# CH32F207VCT6-R1.net
KiCad netlist of a schematic drawn in Altium Designer
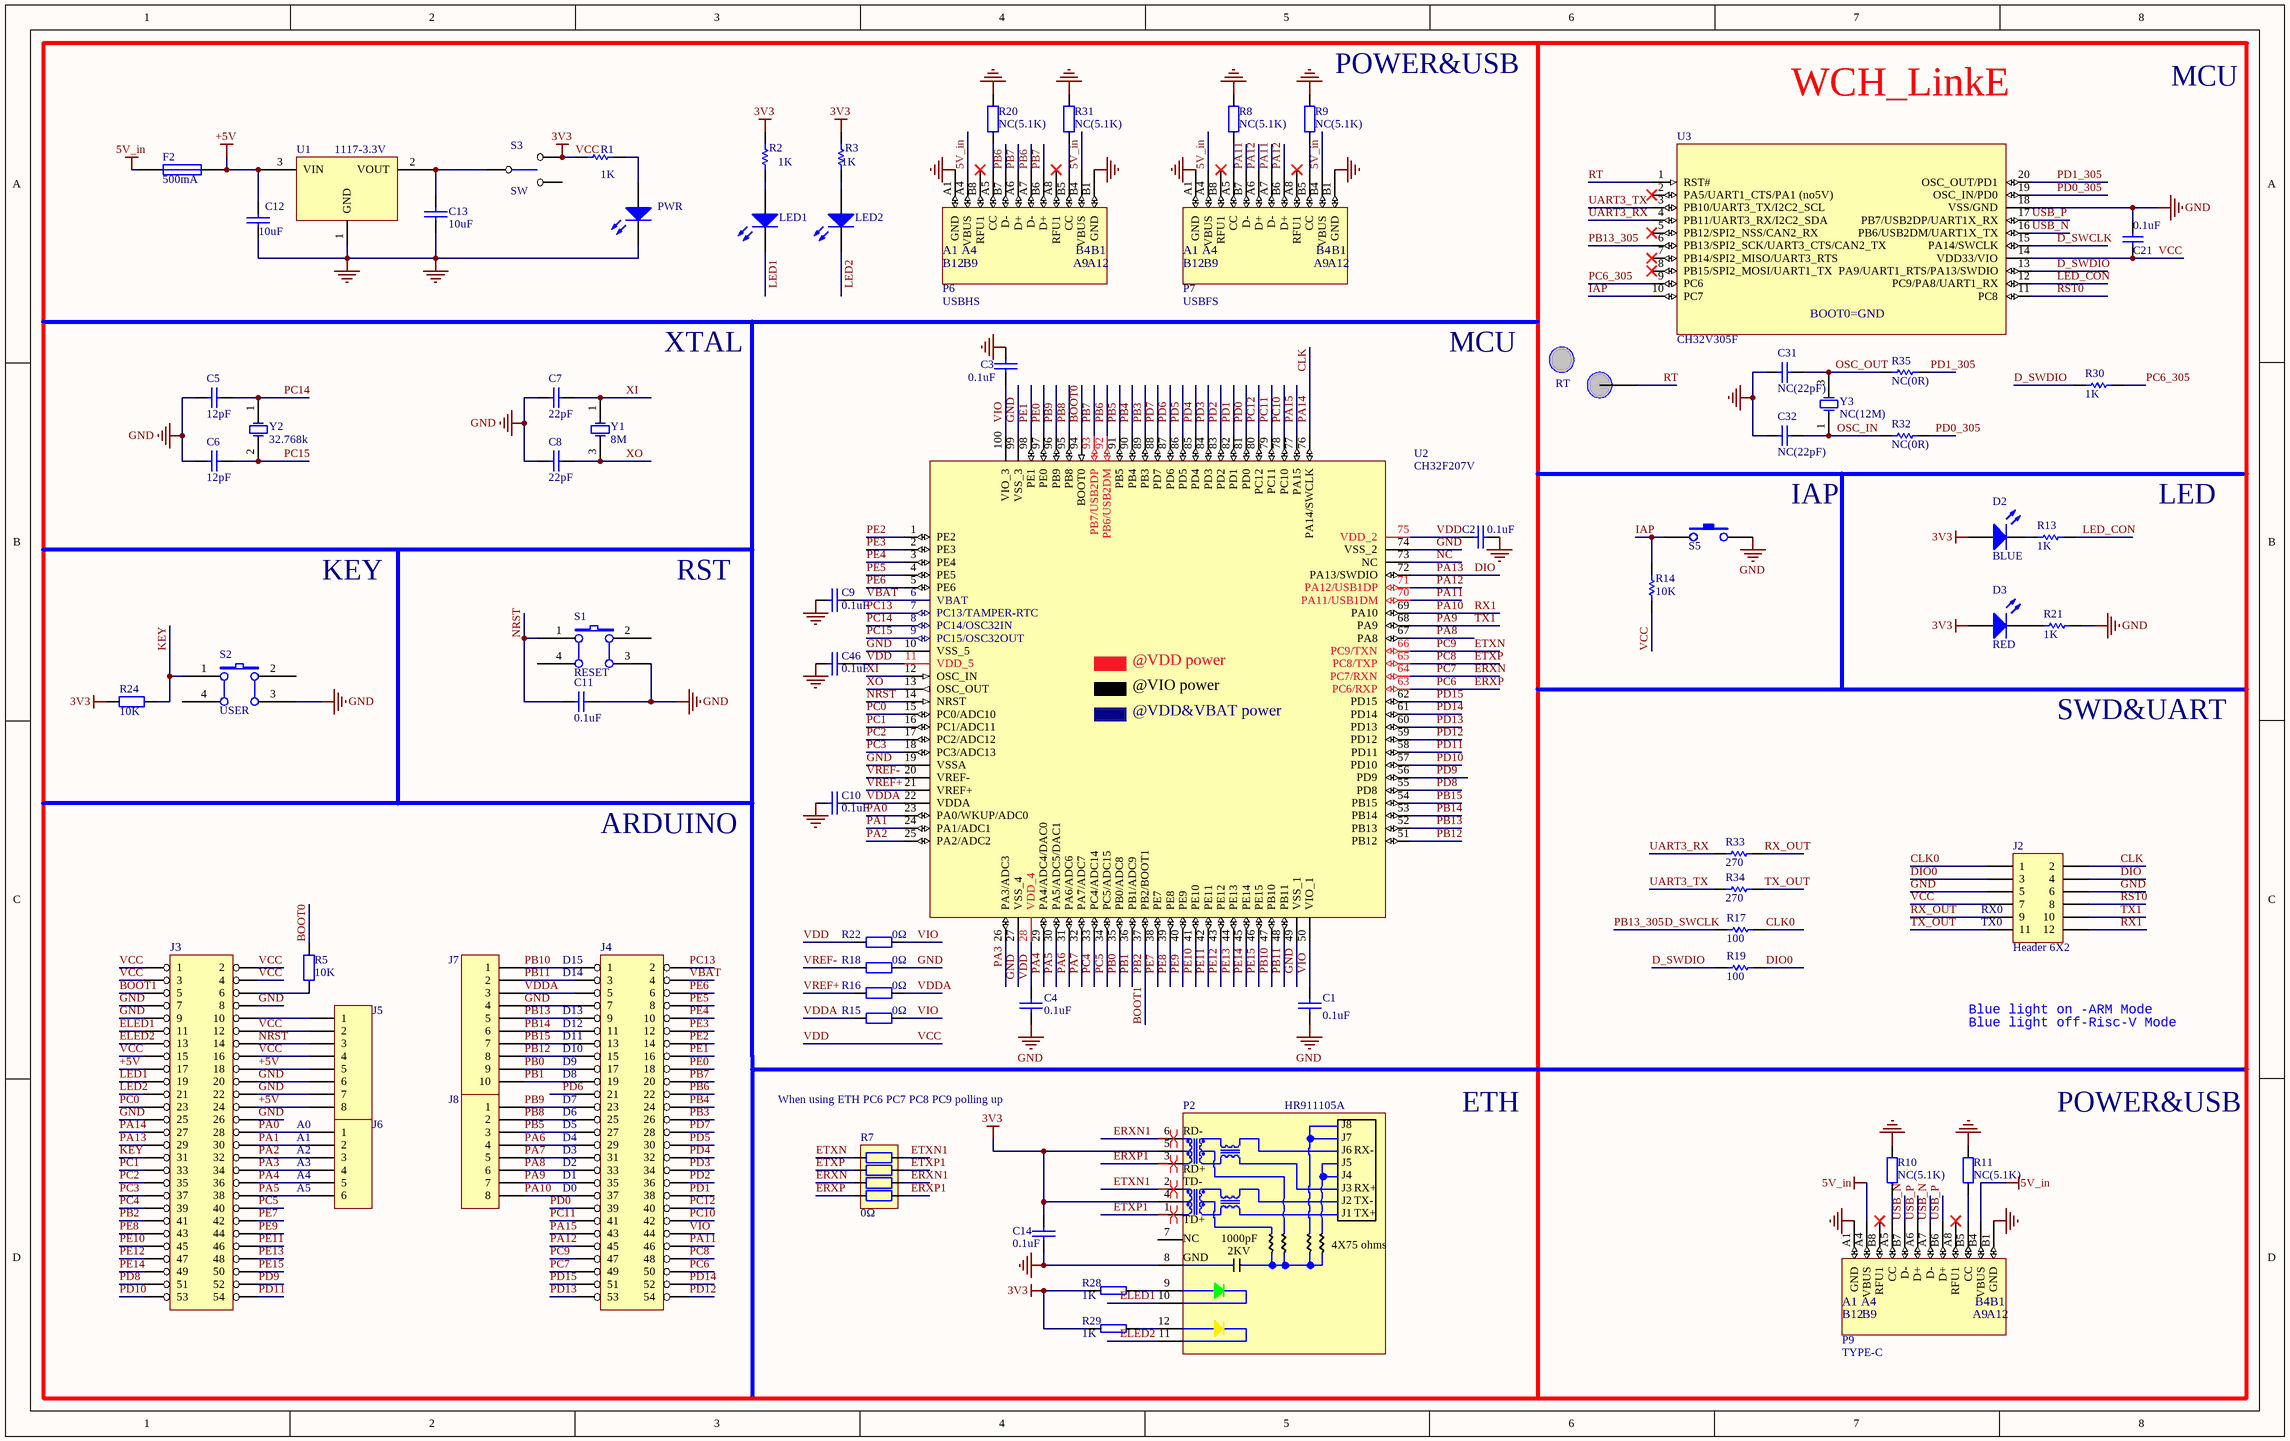
[diagram p0: CH32F207VCT6-R1.SchDoc]

(export (version "E")
  (design (tool "Eeschema 10.0.6"))
  (components
    (comp (ref "C1")
      (value "0.1uF")
      (footprint "0603_C")
      (description "Capacitor")
      (libsource (lib "*") (part "CAP"))
    )
    (comp (ref "C2")
      (value "0.1uF")
      (footprint "0603_C")
      (description "Capacitor")
      (libsource (lib "*") (part "CAP"))
    )
    (comp (ref "C3")
      (value "0.1uF")
      (footprint "0603_C")
      (description "Capacitor")
      (libsource (lib "*") (part "CAP"))
    )
    (comp (ref "C4")
      (value "0.1uF")
      (footprint "0603_C")
      (description "Capacitor")
      (libsource (lib "*") (part "CAP"))
    )
    (comp (ref "C5")
      (value "12pF")
      (footprint "0603_C")
      (description "Capacitor")
      (libsource (lib "Miscellaneous Devices") (part "Cap"))
    )
    (comp (ref "C6")
      (value "12pF")
      (footprint "0603_C")
      (description "Capacitor")
      (libsource (lib "Miscellaneous Devices") (part "Cap"))
    )
    (comp (ref "C7")
      (value "22pF")
      (footprint "0603_C")
      (description "Capacitor")
      (libsource (lib "Miscellaneous Devices") (part "Cap"))
    )
    (comp (ref "C8")
      (value "22pF")
      (footprint "0603_C")
      (description "Capacitor")
      (libsource (lib "Miscellaneous Devices") (part "Cap"))
    )
    (comp (ref "C9")
      (value "0.1uF")
      (footprint "0603_C")
      (description "Capacitor")
      (libsource (lib "*") (part "CAP"))
    )
    (comp (ref "C10")
      (value "0.1uF")
      (footprint "0603_C")
      (description "Capacitor")
      (libsource (lib "*") (part "CAP"))
    )
    (comp (ref "C11")
      (value "0.1uF")
      (footprint "0603_C")
      (description "Capacitor")
      (libsource (lib "Miscellaneous Devices") (part "Cap"))
    )
    (comp (ref "C12")
      (value "10uF")
      (footprint "3216_C")
      (description "Capacitor")
      (libsource (lib "*") (part "CAP"))
    )
    (comp (ref "C13")
      (value "10uF")
      (footprint "3216_C")
      (description "Capacitor")
      (libsource (lib "*") (part "CAP"))
    )
    (comp (ref "C14")
      (value "0.1uF")
      (footprint "0603_C")
      (description "Capacitor")
      (libsource (lib "*") (part "CAP"))
    )
    (comp (ref "C21")
      (value "0.1uF")
      (footprint "0603_C")
      (description "Capacitor")
      (libsource (lib "Miscellaneous Devices") (part "Cap"))
    )
    (comp (ref "C31")
      (value "NC(22pF)")
      (footprint "0603_C")
      (description "Capacitor")
      (libsource (lib "*") (part "Cap"))
    )
    (comp (ref "C32")
      (value "NC(22pF)")
      (footprint "0603_C")
      (description "Capacitor")
      (libsource (lib "*") (part "Cap"))
    )
    (comp (ref "C46")
      (value "0.1uF")
      (footprint "0603_C")
      (description "Capacitor")
      (libsource (lib "*") (part "CAP"))
    )
    (comp (ref "D2")
      (value "BLUE")
      (footprint "0603+")
      (description "Typical RED, GREEN, YELLOW, AMBER GaAs LED")
      (libsource (lib "MYLIB") (part "D0603"))
    )
    (comp (ref "D3")
      (value "RED")
      (footprint "0603+")
      (description "Typical RED, GREEN, YELLOW, AMBER GaAs LED")
      (libsource (lib "MYLIB") (part "D0603"))
    )
    (comp (ref "F2")
      (value "500mA")
      (footprint "0805")
      (description "Fuse")
      (libsource (lib "*") (part "FUSE1"))
    )
    (comp (ref "J2")
      (value "Header 6X2")
      (footprint "IDC12-2.54mm")
      (description "Header, 6-Pin, Dual row")
      (libsource (lib "Miscellaneous Connectors") (part "Header 6X2"))
    )
    (comp (ref "J3")
      (value "HEADER 27x2")
      (footprint "MYPCB:IDC54-2.54MM")
      (description "Header, 27-Pin, Dual row")
      (libsource (lib "wch_sch_others") (part "HEADER 27x2"))
    )
    (comp (ref "J4")
      (value "HEADER 27x2")
      (footprint "MYPCB:IDC54-2.54MM")
      (description "Header, 27-Pin, Dual row")
      (libsource (lib "wch_sch_others") (part "HEADER 27x2"))
    )
    (comp (ref "J5")
      (value "Header 8")
      (footprint "SIP8-2.54mm")
      (description "Header, 8-Pin")
      (libsource (lib "Miscellaneous Connectors") (part "Header 8"))
    )
    (comp (ref "J6")
      (value "Header 6")
      (footprint "SIP6-2.54MM")
      (description "Header, 6-Pin")
      (libsource (lib "Miscellaneous Connectors") (part "Header 6"))
    )
    (comp (ref "J7")
      (value "Header 10")
      (footprint "SIP10-2.54mm")
      (description "Header, 10-Pin")
      (libsource (lib "Miscellaneous Connectors") (part "Header 10"))
    )
    (comp (ref "J8")
      (value "Header 8")
      (footprint "SIP8-2.54mm")
      (description "Header, 8-Pin")
      (libsource (lib "") (part "Header 8_1"))
    )
    (comp (ref "LED1")
      (value "LED1   blue")
      (footprint "0603+")
      (description "Typical INFRARED GaAs LED")
      (libsource (lib "Miscellaneous Devices") (part "LED0"))
    )
    (comp (ref "LED2")
      (value "LED2  blue")
      (footprint "0603+")
      (description "Typical INFRARED GaAs LED")
      (libsource (lib "Miscellaneous Devices") (part "LED0"))
    )
    (comp (ref "P2") (value "HR911105A") (footprint "HR911105A") (libsource (lib "*") (part "HR911105A")))
    (comp (ref "P6")
      (value "USBHS")
      (footprint "TYPE-C-Receptacle-2.0")
      (libsource (lib "*") (part "TYPE-C1"))
    )
    (comp (ref "P7")
      (value "USBFS")
      (footprint "TYPE-C-Receptacle-2.0")
      (libsource (lib "*") (part "TYPE-C1"))
    )
    (comp (ref "P9")
      (value "TYPE-C")
      (footprint "TYPE-C-Receptacle-2.0")
      (libsource (lib "*") (part "TYPE-C1"))
    )
    (comp (ref "PWR")
      (value "POWER  red")
      (footprint "0603+")
      (description "Typical INFRARED GaAs LED")
      (libsource (lib "Miscellaneous Devices") (part "LED0"))
    )
    (comp (ref "R1")
      (value "1K")
      (footprint "0603")
      (description "Semiconductor Resistor")
      (libsource (lib "Miscellaneous Devices") (part "Res Semi"))
    )
    (comp (ref "R2")
      (value "1K")
      (footprint "0603")
      (description "Semiconductor Resistor")
      (libsource (lib "Miscellaneous Devices") (part "Res Semi"))
    )
    (comp (ref "R3")
      (value "1K")
      (footprint "0603")
      (description "Semiconductor Resistor")
      (libsource (lib "Miscellaneous Devices") (part "Res Semi"))
    )
    (comp (ref "R5")
      (value "10K")
      (footprint "0603")
      (description "Resistor")
      (libsource (lib "") (part "Res2_2"))
    )
    (comp (ref "R7")
      (value "0Ω")
      (footprint "RCA-8P4R-0603")
      (description "贴片网络排阻")
      (libsource (lib "wch_sch_others") (part "R-8P4R"))
    )
    (comp (ref "R8")
      (value "NC(5.1K)")
      (footprint "0603")
      (description "Resistor")
      (libsource (lib "Miscellaneous Devices") (part "Res2"))
    )
    (comp (ref "R9")
      (value "NC(5.1K)")
      (footprint "0603")
      (description "Resistor")
      (libsource (lib "Miscellaneous Devices") (part "Res2"))
    )
    (comp (ref "R10")
      (value "NC(5.1K)")
      (footprint "0603")
      (description "Resistor")
      (libsource (lib "") (part "Res2_2"))
    )
    (comp (ref "R11")
      (value "NC(5.1K)")
      (footprint "0603")
      (description "Resistor")
      (libsource (lib "") (part "Res2_2"))
    )
    (comp (ref "R13")
      (value "1K")
      (footprint "0603")
      (description "Resistor")
      (libsource (lib "MYLIB") (part "0603-1"))
    )
    (comp (ref "R14")
      (value "10K")
      (footprint "0603")
      (description "Resistor")
      (libsource (lib "MYLIB") (part "0603-1"))
    )
    (comp (ref "R15")
      (value "0Ω")
      (footprint "0603")
      (description "Resistor")
      (libsource (lib "") (part "Res2_1"))
    )
    (comp (ref "R16")
      (value "0Ω")
      (footprint "0603")
      (description "Resistor")
      (libsource (lib "") (part "Res2_1"))
    )
    (comp (ref "R17")
      (value "100")
      (footprint "0603")
      (description "Resistor")
      (libsource (lib "MYLIB") (part "0603-1"))
    )
    (comp (ref "R18")
      (value "0Ω")
      (footprint "0603")
      (description "Resistor")
      (libsource (lib "") (part "Res2_1"))
    )
    (comp (ref "R19")
      (value "100")
      (footprint "0603")
      (description "Resistor")
      (libsource (lib "MYLIB") (part "0603-1"))
    )
    (comp (ref "R20")
      (value "NC(5.1K)")
      (footprint "0603")
      (description "Resistor")
      (libsource (lib "Miscellaneous Devices") (part "Res2"))
    )
    (comp (ref "R21")
      (value "1K")
      (footprint "0603")
      (description "Resistor")
      (libsource (lib "MYLIB") (part "0603-1"))
    )
    (comp (ref "R22")
      (value "0Ω")
      (footprint "0603")
      (description "Resistor")
      (libsource (lib "") (part "Res2_1"))
    )
    (comp (ref "R24")
      (value "10K")
      (footprint "0603")
      (description "Resistor")
      (libsource (lib "") (part "Res2_1"))
    )
    (comp (ref "R28") (value "1K") (footprint "0603") (libsource (lib "wch_sch_others") (part "RES")))
    (comp (ref "R29") (value "1K") (footprint "0603") (libsource (lib "wch_sch_others") (part "RES")))
    (comp (ref "R30")
      (value "1K")
      (footprint "0603")
      (description "Resistor")
      (libsource (lib "MYLIB") (part "0603-1"))
    )
    (comp (ref "R31")
      (value "NC(5.1K)")
      (footprint "0603")
      (description "Resistor")
      (libsource (lib "Miscellaneous Devices") (part "Res2"))
    )
    (comp (ref "R32")
      (value "NC(0R)")
      (footprint "0603")
      (description "Resistor")
      (libsource (lib "MYLIB") (part "0603-1"))
    )
    (comp (ref "R33")
      (value "270")
      (footprint "0603")
      (description "Resistor")
      (libsource (lib "MYLIB") (part "0603-1"))
    )
    (comp (ref "R34")
      (value "270")
      (footprint "0603")
      (description "Resistor")
      (libsource (lib "MYLIB") (part "0603-1"))
    )
    (comp (ref "R35")
      (value "NC(0R)")
      (footprint "0603")
      (description "Resistor")
      (libsource (lib "MYLIB") (part "0603-1"))
    )
    (comp (ref "RT")
      (value "Testpoint")
      (footprint "TESTPOINT1")
      (description "测试点")
      (libsource (lib "wch_sch_others") (part "Testpoint"))
    )
    (comp (ref "S1")
      (value "RESET")
      (footprint "KEYX")
      (description "SE PUSHBUTTON")
      (libsource (lib "Documents") (part "SW PUSHBUTTON"))
    )
    (comp (ref "S2")
      (value "USER")
      (footprint "KEYX")
      (description "SE PUSHBUTTON")
      (libsource (lib "Documents") (part "SW PUSHBUTTON"))
    )
    (comp (ref "S3") (value "SW") (footprint "SW1") (libsource (lib "MYSCH") (part "SW")))
    (comp (ref "S5") (value "KEY") (footprint "贴片按键") (libsource (lib "*") (part "KEY")))
    (comp (ref "U1")
      (value "1117-3.3V")
      (footprint "SOT-223")
      (libsource (lib "wch_sch_others") (part "1117-3.3V"))
    )
    (comp (ref "U2")
      (value "CH32F207V")
      (footprint "LQFP100")
      (description "ARM M3 HD-MCU, 144MHz, USB_480M, USB OTG, 1000M Ethernet MAC, 2*CAN")
      (libsource (lib "CHXXX") (part "CH32F207V"))
    )
    (comp (ref "U3")
      (value "CH32V305F")
      (footprint "TSSOP20")
      (description "RISC-V FPU HD-MCU, 144MHz, USB_480M, CAN, UART*2, SPI")
      (libsource (lib "CHXXX") (part "CH32V305F"))
    )
    (comp (ref "Y1")
      (value "8M")
      (footprint "XT3225")
      (description "Crystal Oscillator")
      (libsource (lib "Miscellaneous Devices") (part "XTAL"))
    )
    (comp (ref "Y2")
      (value "32.768k")
      (footprint "FC-135")
      (description "Crystal Oscillator")
      (libsource (lib "") (part "XTAL_1"))
    )
    (comp (ref "Y3")
      (value "NC(12M)")
      (footprint "XT3225")
      (description "Crystal Oscillator")
      (libsource (lib "*") (part "XTAL"))
    )
  )
  (nets
    (net (code "1") (name "+5V") (class "Default")
      (node (ref "C12") (pin "1") (pinfunction "1_1") (pintype "passive"))
      (node (ref "F2") (pin "2") (pinfunction "2_2") (pintype "passive"))
      (node (ref "J3") (pin "17") (pinfunction "17_17") (pintype "passive"))
      (node (ref "J3") (pin "18") (pinfunction "18_18") (pintype "passive"))
      (node (ref "J3") (pin "24") (pinfunction "24_24") (pintype "passive"))
      (node (ref "J5") (pin "5") (pinfunction "5_5") (pintype "passive"))
      (node (ref "J5") (pin "8") (pinfunction "8_8") (pintype "passive"))
      (node (ref "U1") (pin "3") (pinfunction "VIN_3") (pintype "passive"))
    )
    (net (code "2") (name "/BOOT0") (class "Default")
      (node (ref "R5") (pin "2") (pinfunction "2_2") (pintype "passive"))
      (node (ref "U2") (pin "94") (pinfunction "BOOT0_94") (pintype "input"))
    )
    (net (code "3") (name "/BOOT1") (class "Default")
      (node (ref "J3") (pin "41") (pinfunction "41_41") (pintype "passive"))
      (node (ref "J3") (pin "5") (pinfunction "5_5") (pintype "passive"))
      (node (ref "U2") (pin "37") (pinfunction "PB2/BOOT1_37") (pintype "bidirectional"))
    )
    (net (code "4") (name "/CLK") (class "Default")
      (node (ref "J2") (pin "2") (pinfunction "2_2") (pintype "passive"))
      (node (ref "J3") (pin "27") (pinfunction "27_27") (pintype "passive"))
      (node (ref "U2") (pin "76") (pinfunction "PA14/SWCLK_76") (pintype "bidirectional"))
    )
    (net (code "5") (name "/CLK0") (class "Default")
      (node (ref "J2") (pin "1") (pinfunction "1_1") (pintype "passive"))
      (node (ref "R17") (pin "1") (pinfunction "1_1") (pintype "passive"))
    )
    (net (code "6") (name "/DIO") (class "Default")
      (node (ref "J2") (pin "4") (pinfunction "4_4") (pintype "passive"))
      (node (ref "J3") (pin "29") (pinfunction "29_29") (pintype "passive"))
      (node (ref "U2") (pin "72") (pinfunction "PA13/SWDIO_72") (pintype "bidirectional"))
    )
    (net (code "7") (name "/DIO0") (class "Default")
      (node (ref "J2") (pin "3") (pinfunction "3_3") (pintype "passive"))
      (node (ref "R19") (pin "1") (pinfunction "1_1") (pintype "passive"))
    )
    (net (code "8") (name "/D_SWCLK") (class "Default")
      (node (ref "R17") (pin "2") (pinfunction "2_2") (pintype "passive"))
      (node (ref "U3") (pin "15") (pinfunction "PA14/SWCLK_15") (pintype "bidirectional"))
      (node (ref "U3") (pin "6") (pinfunction "PB13/SPI2_SCK/UART3_CTS/CAN2_TX_6") (pintype "bidirectional"))
    )
    (net (code "9") (name "/D_SWDIO") (class "Default")
      (node (ref "R19") (pin "2") (pinfunction "2_2") (pintype "passive"))
      (node (ref "R30") (pin "1") (pinfunction "1_1") (pintype "passive"))
      (node (ref "U3") (pin "13") (pinfunction "PA9/UART1_RTS/PA13/SWDIO_13") (pintype "bidirectional"))
    )
    (net (code "10") (name "/ELED1") (class "Default")
      (node (ref "J3") (pin "11") (pinfunction "11_11") (pintype "passive"))
      (node (ref "P2") (pin "10") (pintype "passive"))
    )
    (net (code "11") (name "/ELED2") (class "Default")
      (node (ref "J3") (pin "13") (pinfunction "13_13") (pintype "passive"))
      (node (ref "P2") (pin "11") (pintype "passive"))
    )
    (net (code "12") (name "/ERXN") (class "Default")
      (node (ref "J4") (pin "49") (pinfunction "49_49") (pintype "passive"))
      (node (ref "R7") (pin "3") (pinfunction "3_3") (pintype "passive"))
      (node (ref "U2") (pin "64") (pinfunction "PC7/RXN_64") (pintype "bidirectional"))
    )
    (net (code "13") (name "/ERXN1") (class "Default")
      (node (ref "P2") (pin "6") (pintype "passive"))
      (node (ref "R7") (pin "6") (pinfunction "6_6") (pintype "passive"))
    )
    (net (code "14") (name "/ERXP") (class "Default")
      (node (ref "J4") (pin "50") (pinfunction "50_50") (pintype "passive"))
      (node (ref "R7") (pin "4") (pinfunction "4_4") (pintype "passive"))
      (node (ref "U2") (pin "63") (pinfunction "PC6/RXP_63") (pintype "bidirectional"))
    )
    (net (code "15") (name "/ERXP1") (class "Default")
      (node (ref "P2") (pin "3") (pintype "passive"))
      (node (ref "R7") (pin "5") (pinfunction "5_5") (pintype "passive"))
    )
    (net (code "16") (name "/ETXN") (class "Default")
      (node (ref "J4") (pin "47") (pinfunction "47_47") (pintype "passive"))
      (node (ref "R7") (pin "1") (pinfunction "1_1") (pintype "passive"))
      (node (ref "U2") (pin "66") (pinfunction "PC9/TXN_66") (pintype "bidirectional"))
    )
    (net (code "17") (name "/ETXN1") (class "Default")
      (node (ref "P2") (pin "2") (pintype "passive"))
      (node (ref "R7") (pin "8") (pinfunction "8_8") (pintype "passive"))
    )
    (net (code "18") (name "/ETXP") (class "Default")
      (node (ref "J4") (pin "48") (pinfunction "48_48") (pintype "passive"))
      (node (ref "R7") (pin "2") (pinfunction "2_2") (pintype "passive"))
      (node (ref "U2") (pin "65") (pinfunction "PC8/TXP_65") (pintype "bidirectional"))
    )
    (net (code "19") (name "/ETXP1") (class "Default")
      (node (ref "P2") (pin "1") (pintype "passive"))
      (node (ref "R7") (pin "7") (pinfunction "7_7") (pintype "passive"))
    )
    (net (code "20") (name "/IAP") (class "Default")
      (node (ref "R14") (pin "1") (pinfunction "1_1") (pintype "passive"))
      (node (ref "S5") (pin "1") (pinfunction "1_1") (pintype "passive"))
      (node (ref "U3") (pin "10") (pinfunction "PC7_10") (pintype "bidirectional"))
    )
    (net (code "21") (name "/KEY") (class "Default")
      (node (ref "J3") (pin "31") (pinfunction "31_31") (pintype "passive"))
      (node (ref "R24") (pin "1") (pinfunction "1_1") (pintype "passive"))
      (node (ref "S2") (pin "1") (pinfunction "A0_1") (pintype "passive"))
    )
    (net (code "22") (name "/LED1") (class "Default")
      (node (ref "J3") (pin "19") (pinfunction "19_19") (pintype "passive"))
      (node (ref "LED1") (pin "2") (pinfunction "K_2") (pintype "passive"))
    )
    (net (code "23") (name "/LED2") (class "Default")
      (node (ref "J3") (pin "21") (pinfunction "21_21") (pintype "passive"))
      (node (ref "LED2") (pin "2") (pinfunction "K_2") (pintype "passive"))
    )
    (net (code "24") (name "/LED_CON") (class "Default")
      (node (ref "R13") (pin "1") (pinfunction "1_1") (pintype "passive"))
      (node (ref "U3") (pin "12") (pinfunction "PC9/PA8/UART1_RX_12") (pintype "bidirectional"))
    )
    (net (code "25") (name "/NC") (class "Default")
      (node (ref "U2") (pin "73") (pinfunction "NC_73") (pintype "tri_state"))
    )
    (net (code "26") (name "/NRST") (class "Default")
      (node (ref "C11") (pin "2") (pinfunction "2_2") (pintype "passive"))
      (node (ref "J3") (pin "14") (pinfunction "14_14") (pintype "passive"))
      (node (ref "J5") (pin "3") (pinfunction "3_3") (pintype "passive"))
      (node (ref "S1") (pin "1") (pinfunction "A0_1") (pintype "passive"))
      (node (ref "U2") (pin "14") (pinfunction "NRST_14") (pintype "input"))
    )
    (net (code "27") (name "/OSC_IN") (class "Default")
      (node (ref "C32") (pin "2") (pinfunction "2_2") (pintype "passive"))
      (node (ref "R32") (pin "2") (pinfunction "2_2") (pintype "passive"))
      (node (ref "Y3") (pin "1") (pinfunction "OSC1_1") (pintype "passive"))
    )
    (net (code "28") (name "/OSC_OUT") (class "Default")
      (node (ref "C31") (pin "2") (pinfunction "2_2") (pintype "passive"))
      (node (ref "R35") (pin "2") (pinfunction "2_2") (pintype "passive"))
      (node (ref "Y3") (pin "3") (pinfunction "OSC2_3") (pintype "passive"))
    )
    (net (code "29") (name "/PA0") (class "Default")
      (node (ref "J3") (pin "28") (pinfunction "28_28") (pintype "passive"))
      (node (ref "J6") (pin "1") (pinfunction "1_1") (pintype "passive"))
      (node (ref "U2") (pin "23") (pinfunction "PA0/WKUP/ADC0_23") (pintype "bidirectional"))
    )
    (net (code "30") (name "/PA1") (class "Default")
      (node (ref "J3") (pin "30") (pinfunction "30_30") (pintype "passive"))
      (node (ref "J6") (pin "2") (pinfunction "2_2") (pintype "passive"))
      (node (ref "U2") (pin "24") (pinfunction "PA1/ADC1_24") (pintype "bidirectional"))
    )
    (net (code "31") (name "/PA2") (class "Default")
      (node (ref "J3") (pin "32") (pinfunction "32_32") (pintype "passive"))
      (node (ref "J6") (pin "3") (pinfunction "3_3") (pintype "passive"))
      (node (ref "U2") (pin "25") (pinfunction "PA2/ADC2_25") (pintype "bidirectional"))
    )
    (net (code "32") (name "/PA3") (class "Default")
      (node (ref "J3") (pin "34") (pinfunction "34_34") (pintype "passive"))
      (node (ref "J6") (pin "4") (pinfunction "4_4") (pintype "passive"))
      (node (ref "U2") (pin "26") (pinfunction "PA3/ADC3_26") (pintype "bidirectional"))
    )
    (net (code "33") (name "/PA4") (class "Default")
      (node (ref "J3") (pin "36") (pinfunction "36_36") (pintype "passive"))
      (node (ref "J6") (pin "5") (pinfunction "5_5") (pintype "passive"))
      (node (ref "U2") (pin "29") (pinfunction "PA4/ADC4/DAC0_29") (pintype "bidirectional"))
    )
    (net (code "34") (name "/PA5") (class "Default")
      (node (ref "J3") (pin "38") (pinfunction "38_38") (pintype "passive"))
      (node (ref "J6") (pin "6") (pinfunction "6_6") (pintype "passive"))
      (node (ref "U2") (pin "30") (pinfunction "PA5/ADC5/DAC1_30") (pintype "bidirectional"))
    )
    (net (code "35") (name "/PA6") (class "Default")
      (node (ref "J4") (pin "29") (pinfunction "29_29") (pintype "passive"))
      (node (ref "J8") (pin "4") (pinfunction "4_4") (pintype "passive"))
      (node (ref "U2") (pin "31") (pinfunction "PA6/ADC6_31") (pintype "bidirectional"))
    )
    (net (code "36") (name "/PA7") (class "Default")
      (node (ref "J4") (pin "31") (pinfunction "31_31") (pintype "passive"))
      (node (ref "J8") (pin "5") (pinfunction "5_5") (pintype "passive"))
      (node (ref "U2") (pin "32") (pinfunction "PA7/ADC7_32") (pintype "bidirectional"))
    )
    (net (code "37") (name "/PA8") (class "Default")
      (node (ref "J4") (pin "33") (pinfunction "33_33") (pintype "passive"))
      (node (ref "J8") (pin "6") (pinfunction "6_6") (pintype "passive"))
      (node (ref "U2") (pin "67") (pinfunction "PA8_67") (pintype "bidirectional"))
    )
    (net (code "38") (name "/PA9") (class "Default")
      (node (ref "J2") (pin "10") (pinfunction "10_10") (pintype "passive"))
      (node (ref "J4") (pin "35") (pinfunction "35_35") (pintype "passive"))
      (node (ref "J8") (pin "7") (pinfunction "7_7") (pintype "passive"))
      (node (ref "U2") (pin "68") (pinfunction "PA9_68") (pintype "bidirectional"))
    )
    (net (code "39") (name "/PA10") (class "Default")
      (node (ref "J2") (pin "12") (pinfunction "12_12") (pintype "passive"))
      (node (ref "J4") (pin "37") (pinfunction "37_37") (pintype "passive"))
      (node (ref "J8") (pin "8") (pinfunction "8_8") (pintype "passive"))
      (node (ref "U2") (pin "69") (pinfunction "PA10_69") (pintype "bidirectional"))
    )
    (net (code "40") (name "/PA11") (class "Default")
      (node (ref "J4") (pin "46") (pinfunction "46_46") (pintype "passive"))
      (node (ref "P7") (pin "A7") (pinfunction "D-_A7") (pintype "bidirectional"))
      (node (ref "P7") (pin "B7") (pinfunction "D-_B7") (pintype "bidirectional"))
      (node (ref "U2") (pin "70") (pinfunction "PA11/USB1DM_70") (pintype "bidirectional"))
    )
    (net (code "41") (name "/PA12") (class "Default")
      (node (ref "J4") (pin "45") (pinfunction "45_45") (pintype "passive"))
      (node (ref "P7") (pin "A6") (pinfunction "D+_A6") (pintype "bidirectional"))
      (node (ref "P7") (pin "B6") (pinfunction "D+_B6") (pintype "bidirectional"))
      (node (ref "U2") (pin "71") (pinfunction "PA12/USB1DP_71") (pintype "bidirectional"))
    )
    (net (code "42") (name "/PA15") (class "Default")
      (node (ref "J4") (pin "43") (pinfunction "43_43") (pintype "passive"))
      (node (ref "U2") (pin "77") (pinfunction "PA15_77") (pintype "bidirectional"))
    )
    (net (code "43") (name "/PB0") (class "Default")
      (node (ref "J4") (pin "17") (pinfunction "17_17") (pintype "passive"))
      (node (ref "J7") (pin "9") (pinfunction "9_9") (pintype "passive"))
      (node (ref "U2") (pin "35") (pinfunction "PB0/ADC8_35") (pintype "bidirectional"))
    )
    (net (code "44") (name "/PB1") (class "Default")
      (node (ref "J4") (pin "19") (pinfunction "19_19") (pintype "passive"))
      (node (ref "J7") (pin "10") (pinfunction "10_10") (pintype "passive"))
      (node (ref "U2") (pin "36") (pinfunction "PB1/ADC9_36") (pintype "bidirectional"))
    )
    (net (code "45") (name "/PB3") (class "Default")
      (node (ref "J4") (pin "26") (pinfunction "26_26") (pintype "passive"))
      (node (ref "U2") (pin "89") (pinfunction "PB3_89") (pintype "bidirectional"))
    )
    (net (code "46") (name "/PB4") (class "Default")
      (node (ref "J4") (pin "24") (pinfunction "24_24") (pintype "passive"))
      (node (ref "U2") (pin "90") (pinfunction "PB4_90") (pintype "bidirectional"))
    )
    (net (code "47") (name "/PB5") (class "Default")
      (node (ref "J4") (pin "27") (pinfunction "27_27") (pintype "passive"))
      (node (ref "J8") (pin "3") (pinfunction "3_3") (pintype "passive"))
      (node (ref "U2") (pin "91") (pinfunction "PB5_91") (pintype "bidirectional"))
    )
    (net (code "48") (name "/PB6") (class "Default")
      (node (ref "J4") (pin "22") (pinfunction "22_22") (pintype "passive"))
      (node (ref "P6") (pin "A7") (pinfunction "D-_A7") (pintype "bidirectional"))
      (node (ref "P6") (pin "B7") (pinfunction "D-_B7") (pintype "bidirectional"))
      (node (ref "U2") (pin "92") (pinfunction "PB6/USB2DM_92") (pintype "bidirectional"))
    )
    (net (code "49") (name "/PB7") (class "Default")
      (node (ref "J4") (pin "20") (pinfunction "20_20") (pintype "passive"))
      (node (ref "P6") (pin "A6") (pinfunction "D+_A6") (pintype "bidirectional"))
      (node (ref "P6") (pin "B6") (pinfunction "D+_B6") (pintype "bidirectional"))
      (node (ref "U2") (pin "93") (pinfunction "PB7/USB2DP_93") (pintype "bidirectional"))
    )
    (net (code "50") (name "/PB8") (class "Default")
      (node (ref "J4") (pin "25") (pinfunction "25_25") (pintype "passive"))
      (node (ref "J8") (pin "2") (pinfunction "2_2") (pintype "passive"))
      (node (ref "U2") (pin "95") (pinfunction "PB8_95") (pintype "bidirectional"))
    )
    (net (code "51") (name "/PB9") (class "Default")
      (node (ref "J4") (pin "23") (pinfunction "23_23") (pintype "passive"))
      (node (ref "J8") (pin "1") (pinfunction "1_1") (pintype "passive"))
      (node (ref "U2") (pin "96") (pinfunction "PB9_96") (pintype "bidirectional"))
    )
    (net (code "52") (name "/PB10") (class "Default")
      (node (ref "J4") (pin "1") (pinfunction "1_1") (pintype "passive"))
      (node (ref "J7") (pin "1") (pinfunction "1_1") (pintype "passive"))
      (node (ref "U2") (pin "47") (pinfunction "PB10_47") (pintype "bidirectional"))
    )
    (net (code "53") (name "/PB11") (class "Default")
      (node (ref "J4") (pin "3") (pinfunction "3_3") (pintype "passive"))
      (node (ref "J7") (pin "2") (pinfunction "2_2") (pintype "passive"))
      (node (ref "U2") (pin "48") (pinfunction "PB11_48") (pintype "bidirectional"))
    )
    (net (code "54") (name "/PB12") (class "Default")
      (node (ref "J4") (pin "15") (pinfunction "15_15") (pintype "passive"))
      (node (ref "J7") (pin "8") (pinfunction "8_8") (pintype "passive"))
      (node (ref "U2") (pin "51") (pinfunction "PB12_51") (pintype "bidirectional"))
    )
    (net (code "55") (name "/PB13") (class "Default")
      (node (ref "J4") (pin "9") (pinfunction "9_9") (pintype "passive"))
      (node (ref "J7") (pin "5") (pinfunction "5_5") (pintype "passive"))
      (node (ref "U2") (pin "52") (pinfunction "PB13_52") (pintype "bidirectional"))
    )
    (net (code "56") (name "/PB14") (class "Default")
      (node (ref "J4") (pin "11") (pinfunction "11_11") (pintype "passive"))
      (node (ref "J7") (pin "6") (pinfunction "6_6") (pintype "passive"))
      (node (ref "U2") (pin "53") (pinfunction "PB14_53") (pintype "bidirectional"))
    )
    (net (code "57") (name "/PB15") (class "Default")
      (node (ref "J4") (pin "13") (pinfunction "13_13") (pintype "passive"))
      (node (ref "J7") (pin "7") (pinfunction "7_7") (pintype "passive"))
      (node (ref "U2") (pin "54") (pinfunction "PB15_54") (pintype "bidirectional"))
    )
    (net (code "58") (name "/PC0") (class "Default")
      (node (ref "J3") (pin "23") (pinfunction "23_23") (pintype "passive"))
      (node (ref "U2") (pin "15") (pinfunction "PC0/ADC10_15") (pintype "bidirectional"))
    )
    (net (code "59") (name "/PC1") (class "Default")
      (node (ref "J3") (pin "33") (pinfunction "33_33") (pintype "passive"))
      (node (ref "U2") (pin "16") (pinfunction "PC1/ADC11_16") (pintype "bidirectional"))
    )
    (net (code "60") (name "/PC2") (class "Default")
      (node (ref "J3") (pin "35") (pinfunction "35_35") (pintype "passive"))
      (node (ref "U2") (pin "17") (pinfunction "PC2/ADC12_17") (pintype "bidirectional"))
    )
    (net (code "61") (name "/PC3") (class "Default")
      (node (ref "J3") (pin "37") (pinfunction "37_37") (pintype "passive"))
      (node (ref "U2") (pin "18") (pinfunction "PC3/ADC13_18") (pintype "bidirectional"))
    )
    (net (code "62") (name "/PC4") (class "Default")
      (node (ref "J3") (pin "39") (pinfunction "39_39") (pintype "passive"))
      (node (ref "U2") (pin "33") (pinfunction "PC4/ADC14_33") (pintype "bidirectional"))
    )
    (net (code "63") (name "/PC5") (class "Default")
      (node (ref "J3") (pin "40") (pinfunction "40_40") (pintype "passive"))
      (node (ref "U2") (pin "34") (pinfunction "PC5/ADC15_34") (pintype "bidirectional"))
    )
    (net (code "64") (name "/PC6_305") (class "Default")
      (node (ref "R30") (pin "2") (pinfunction "2_2") (pintype "passive"))
      (node (ref "U3") (pin "9") (pinfunction "PC6_9") (pintype "bidirectional"))
    )
    (net (code "65") (name "/PC10") (class "Default")
      (node (ref "J4") (pin "42") (pinfunction "42_42") (pintype "passive"))
      (node (ref "U2") (pin "78") (pinfunction "PC10_78") (pintype "bidirectional"))
    )
    (net (code "66") (name "/PC11") (class "Default")
      (node (ref "J4") (pin "41") (pinfunction "41_41") (pintype "passive"))
      (node (ref "U2") (pin "79") (pinfunction "PC11_79") (pintype "bidirectional"))
    )
    (net (code "67") (name "/PC12") (class "Default")
      (node (ref "J4") (pin "40") (pinfunction "40_40") (pintype "passive"))
      (node (ref "U2") (pin "80") (pinfunction "PC12_80") (pintype "bidirectional"))
    )
    (net (code "68") (name "/PC13") (class "Default")
      (node (ref "J4") (pin "2") (pinfunction "2_2") (pintype "passive"))
      (node (ref "U2") (pin "7") (pinfunction "PC13/TAMPER-RTC_7") (pintype "bidirectional"))
    )
    (net (code "69") (name "/PC14") (class "Default")
      (node (ref "C5") (pin "1") (pinfunction "1_1") (pintype "passive"))
      (node (ref "U2") (pin "8") (pinfunction "PC14/OSC32IN_8") (pintype "bidirectional"))
      (node (ref "Y2") (pin "1") (pinfunction "OSC1_1") (pintype "passive"))
    )
    (net (code "70") (name "/PC15") (class "Default")
      (node (ref "C6") (pin "1") (pinfunction "1_1") (pintype "passive"))
      (node (ref "U2") (pin "9") (pinfunction "PC15/OSC32OUT_9") (pintype "bidirectional"))
      (node (ref "Y2") (pin "2") (pinfunction "OSC2_2") (pintype "passive"))
    )
    (net (code "71") (name "/PD0") (class "Default")
      (node (ref "J4") (pin "39") (pinfunction "39_39") (pintype "passive"))
      (node (ref "U2") (pin "81") (pinfunction "PD0_81") (pintype "bidirectional"))
    )
    (net (code "72") (name "/PD0_305") (class "Default")
      (node (ref "R32") (pin "1") (pinfunction "1_1") (pintype "passive"))
      (node (ref "U3") (pin "19") (pinfunction "OSC_IN/PD0_19") (pintype "bidirectional"))
    )
    (net (code "73") (name "/PD1") (class "Default")
      (node (ref "J4") (pin "38") (pinfunction "38_38") (pintype "passive"))
      (node (ref "U2") (pin "82") (pinfunction "PD1_82") (pintype "bidirectional"))
    )
    (net (code "74") (name "/PD1_305") (class "Default")
      (node (ref "R35") (pin "1") (pinfunction "1_1") (pintype "passive"))
      (node (ref "U3") (pin "20") (pinfunction "OSC_OUT/PD1_20") (pintype "bidirectional"))
    )
    (net (code "75") (name "/PD2") (class "Default")
      (node (ref "J4") (pin "36") (pinfunction "36_36") (pintype "passive"))
      (node (ref "U2") (pin "83") (pinfunction "PD2_83") (pintype "bidirectional"))
    )
    (net (code "76") (name "/PD3") (class "Default")
      (node (ref "J4") (pin "34") (pinfunction "34_34") (pintype "passive"))
      (node (ref "U2") (pin "84") (pinfunction "PD3_84") (pintype "bidirectional"))
    )
    (net (code "77") (name "/PD4") (class "Default")
      (node (ref "J4") (pin "32") (pinfunction "32_32") (pintype "passive"))
      (node (ref "U2") (pin "85") (pinfunction "PD4_85") (pintype "bidirectional"))
    )
    (net (code "78") (name "/PD5") (class "Default")
      (node (ref "J4") (pin "30") (pinfunction "30_30") (pintype "passive"))
      (node (ref "U2") (pin "86") (pinfunction "PD5_86") (pintype "bidirectional"))
    )
    (net (code "79") (name "/PD6") (class "Default")
      (node (ref "J4") (pin "21") (pinfunction "21_21") (pintype "passive"))
      (node (ref "U2") (pin "87") (pinfunction "PD6_87") (pintype "bidirectional"))
    )
    (net (code "80") (name "/PD7") (class "Default")
      (node (ref "J4") (pin "28") (pinfunction "28_28") (pintype "passive"))
      (node (ref "U2") (pin "88") (pinfunction "PD7_88") (pintype "bidirectional"))
    )
    (net (code "81") (name "/PD8") (class "Default")
      (node (ref "J3") (pin "51") (pinfunction "51_51") (pintype "passive"))
      (node (ref "U2") (pin "55") (pinfunction "PD8_55") (pintype "bidirectional"))
    )
    (net (code "82") (name "/PD9") (class "Default")
      (node (ref "J3") (pin "52") (pinfunction "52_52") (pintype "passive"))
      (node (ref "U2") (pin "56") (pinfunction "PD9_56") (pintype "bidirectional"))
    )
    (net (code "83") (name "/PD10") (class "Default")
      (node (ref "J3") (pin "53") (pinfunction "53_53") (pintype "passive"))
      (node (ref "U2") (pin "57") (pinfunction "PD10_57") (pintype "bidirectional"))
    )
    (net (code "84") (name "/PD11") (class "Default")
      (node (ref "J3") (pin "54") (pinfunction "54_54") (pintype "passive"))
      (node (ref "U2") (pin "58") (pinfunction "PD11_58") (pintype "bidirectional"))
    )
    (net (code "85") (name "/PD12") (class "Default")
      (node (ref "J4") (pin "54") (pinfunction "54_54") (pintype "passive"))
      (node (ref "U2") (pin "59") (pinfunction "PD12_59") (pintype "bidirectional"))
    )
    (net (code "86") (name "/PD13") (class "Default")
      (node (ref "J4") (pin "53") (pinfunction "53_53") (pintype "passive"))
      (node (ref "U2") (pin "60") (pinfunction "PD13_60") (pintype "bidirectional"))
    )
    (net (code "87") (name "/PD14") (class "Default")
      (node (ref "J4") (pin "52") (pinfunction "52_52") (pintype "passive"))
      (node (ref "U2") (pin "61") (pinfunction "PD14_61") (pintype "bidirectional"))
    )
    (net (code "88") (name "/PD15") (class "Default")
      (node (ref "J4") (pin "51") (pinfunction "51_51") (pintype "passive"))
      (node (ref "U2") (pin "62") (pinfunction "PD15_62") (pintype "bidirectional"))
    )
    (net (code "89") (name "/PE0") (class "Default")
      (node (ref "J4") (pin "18") (pinfunction "18_18") (pintype "passive"))
      (node (ref "U2") (pin "97") (pinfunction "PE0_97") (pintype "bidirectional"))
    )
    (net (code "90") (name "/PE1") (class "Default")
      (node (ref "J4") (pin "16") (pinfunction "16_16") (pintype "passive"))
      (node (ref "U2") (pin "98") (pinfunction "PE1_98") (pintype "bidirectional"))
    )
    (net (code "91") (name "/PE2") (class "Default")
      (node (ref "J4") (pin "14") (pinfunction "14_14") (pintype "passive"))
      (node (ref "U2") (pin "1") (pinfunction "PE2_1") (pintype "bidirectional"))
    )
    (net (code "92") (name "/PE3") (class "Default")
      (node (ref "J4") (pin "12") (pinfunction "12_12") (pintype "passive"))
      (node (ref "U2") (pin "2") (pinfunction "PE3_2") (pintype "bidirectional"))
    )
    (net (code "93") (name "/PE4") (class "Default")
      (node (ref "J4") (pin "10") (pinfunction "10_10") (pintype "passive"))
      (node (ref "U2") (pin "3") (pinfunction "PE4_3") (pintype "bidirectional"))
    )
    (net (code "94") (name "/PE5") (class "Default")
      (node (ref "J4") (pin "8") (pinfunction "8_8") (pintype "passive"))
      (node (ref "U2") (pin "4") (pinfunction "PE5_4") (pintype "bidirectional"))
    )
    (net (code "95") (name "/PE6") (class "Default")
      (node (ref "J4") (pin "6") (pinfunction "6_6") (pintype "passive"))
      (node (ref "U2") (pin "5") (pinfunction "PE6_5") (pintype "bidirectional"))
    )
    (net (code "96") (name "/PE7") (class "Default")
      (node (ref "J3") (pin "42") (pinfunction "42_42") (pintype "passive"))
      (node (ref "U2") (pin "38") (pinfunction "PE7_38") (pintype "bidirectional"))
    )
    (net (code "97") (name "/PE8") (class "Default")
      (node (ref "J3") (pin "43") (pinfunction "43_43") (pintype "passive"))
      (node (ref "U2") (pin "39") (pinfunction "PE8_39") (pintype "bidirectional"))
    )
    (net (code "98") (name "/PE9") (class "Default")
      (node (ref "J3") (pin "44") (pinfunction "44_44") (pintype "passive"))
      (node (ref "U2") (pin "40") (pinfunction "PE9_40") (pintype "bidirectional"))
    )
    (net (code "99") (name "/PE10") (class "Default")
      (node (ref "J3") (pin "45") (pinfunction "45_45") (pintype "passive"))
      (node (ref "U2") (pin "41") (pinfunction "PE10_41") (pintype "bidirectional"))
    )
    (net (code "100") (name "/PE11") (class "Default")
      (node (ref "J3") (pin "46") (pinfunction "46_46") (pintype "passive"))
      (node (ref "U2") (pin "42") (pinfunction "PE11_42") (pintype "bidirectional"))
    )
    (net (code "101") (name "/PE12") (class "Default")
      (node (ref "J3") (pin "47") (pinfunction "47_47") (pintype "passive"))
      (node (ref "U2") (pin "43") (pinfunction "PE12_43") (pintype "bidirectional"))
    )
    (net (code "102") (name "/PE13") (class "Default")
      (node (ref "J3") (pin "48") (pinfunction "48_48") (pintype "passive"))
      (node (ref "U2") (pin "44") (pinfunction "PE13_44") (pintype "bidirectional"))
    )
    (net (code "103") (name "/PE14") (class "Default")
      (node (ref "J3") (pin "49") (pinfunction "49_49") (pintype "passive"))
      (node (ref "U2") (pin "45") (pinfunction "PE14_45") (pintype "bidirectional"))
    )
    (net (code "104") (name "/PE15") (class "Default")
      (node (ref "J3") (pin "50") (pinfunction "50_50") (pintype "passive"))
      (node (ref "U2") (pin "46") (pinfunction "PE15_46") (pintype "bidirectional"))
    )
    (net (code "105") (name "/RST0") (class "Default")
      (node (ref "J2") (pin "8") (pinfunction "8_8") (pintype "passive"))
      (node (ref "U3") (pin "11") (pinfunction "PC8_11") (pintype "bidirectional"))
    )
    (net (code "106") (name "/RT") (class "Default")
      (node (ref "RT") (pin "1") (pinfunction "point_1") (pintype "passive"))
      (node (ref "U3") (pin "1") (pinfunction "RST#_1") (pintype "input"))
    )
    (net (code "107") (name "/RX_OUT") (class "Default")
      (node (ref "J2") (pin "9") (pinfunction "9_9") (pintype "passive"))
      (node (ref "R33") (pin "1") (pinfunction "1_1") (pintype "passive"))
    )
    (net (code "108") (name "/TX_OUT") (class "Default")
      (node (ref "J2") (pin "11") (pinfunction "11_11") (pintype "passive"))
      (node (ref "R34") (pin "1") (pinfunction "1_1") (pintype "passive"))
    )
    (net (code "109") (name "/UART3_RX") (class "Default")
      (node (ref "R33") (pin "2") (pinfunction "2_2") (pintype "passive"))
      (node (ref "U3") (pin "4") (pinfunction "PB11/UART3_RX/I2C2_SDA_4") (pintype "bidirectional"))
    )
    (net (code "110") (name "/UART3_TX") (class "Default")
      (node (ref "R34") (pin "2") (pinfunction "2_2") (pintype "passive"))
      (node (ref "U3") (pin "3") (pinfunction "PB10/UART3_TX/I2C2_SCL_3") (pintype "bidirectional"))
    )
    (net (code "111") (name "/USB_N") (class "Default")
      (node (ref "P9") (pin "A7") (pinfunction "D-_A7") (pintype "bidirectional"))
      (node (ref "P9") (pin "B7") (pinfunction "D-_B7") (pintype "bidirectional"))
      (node (ref "U3") (pin "16") (pinfunction "PB6/USB2DM/UART1X_TX_16") (pintype "bidirectional"))
    )
    (net (code "112") (name "/USB_P") (class "Default")
      (node (ref "P9") (pin "A6") (pinfunction "D+_A6") (pintype "bidirectional"))
      (node (ref "P9") (pin "B6") (pinfunction "D+_B6") (pintype "bidirectional"))
      (node (ref "U3") (pin "17") (pinfunction "PB7/USB2DP/UART1X_RX_17") (pintype "bidirectional"))
    )
    (net (code "113") (name "/VBAT") (class "Default")
      (node (ref "C9") (pin "2") (pinfunction "2_2") (pintype "passive"))
      (node (ref "J4") (pin "4") (pinfunction "4_4") (pintype "passive"))
      (node (ref "U2") (pin "6") (pinfunction "VBAT_6") (pintype "power_in"))
    )
    (net (code "114") (name "/VDDA") (class "Default")
      (node (ref "C10") (pin "2") (pinfunction "2_2") (pintype "passive"))
      (node (ref "J4") (pin "5") (pinfunction "5_5") (pintype "passive"))
      (node (ref "J7") (pin "3") (pinfunction "3_3") (pintype "passive"))
      (node (ref "R15") (pin "2") (pinfunction "2_2") (pintype "passive"))
      (node (ref "R16") (pin "1") (pinfunction "1_1") (pintype "passive"))
      (node (ref "U2") (pin "22") (pinfunction "VDDA_22") (pintype "power_in"))
    )
    (net (code "115") (name "/VIO") (class "Default")
      (node (ref "C1") (pin "2") (pinfunction "2_2") (pintype "passive"))
      (node (ref "C3") (pin "1") (pinfunction "1_1") (pintype "passive"))
      (node (ref "J4") (pin "44") (pinfunction "44_44") (pintype "passive"))
      (node (ref "R15") (pin "1") (pinfunction "1_1") (pintype "passive"))
      (node (ref "R22") (pin "1") (pinfunction "1_1") (pintype "passive"))
      (node (ref "U2") (pin "100") (pinfunction "VIO_3_100") (pintype "power_in"))
      (node (ref "U2") (pin "50") (pinfunction "VIO_1_50") (pintype "power_in"))
    )
    (net (code "116") (name "/VREF+") (class "Default")
      (node (ref "R16") (pin "2") (pinfunction "2_2") (pintype "passive"))
      (node (ref "U2") (pin "21") (pinfunction "VREF+_21") (pintype "power_in"))
    )
    (net (code "117") (name "/VREF-") (class "Default")
      (node (ref "R18") (pin "2") (pinfunction "2_2") (pintype "passive"))
      (node (ref "U2") (pin "20") (pinfunction "VREF-_20") (pintype "power_in"))
    )
    (net (code "118") (name "/XI") (class "Default")
      (node (ref "C7") (pin "2") (pinfunction "2_2") (pintype "passive"))
      (node (ref "U2") (pin "12") (pinfunction "OSC_IN_12") (pintype "input"))
      (node (ref "Y1") (pin "1") (pinfunction "OSC1_1") (pintype "passive"))
    )
    (net (code "119") (name "/XO") (class "Default")
      (node (ref "C8") (pin "2") (pinfunction "2_2") (pintype "passive"))
      (node (ref "U2") (pin "13") (pinfunction "OSC_OUT_13") (pintype "output"))
      (node (ref "Y1") (pin "3") (pinfunction "OSC2_3") (pintype "passive"))
    )
    (net (code "120") (name "3V3") (class "Default")
      (node (ref "C14") (pin "2") (pinfunction "2_2") (pintype "passive"))
      (node (ref "C2") (pin "2") (pinfunction "2_2") (pintype "passive"))
      (node (ref "C21") (pin "1") (pinfunction "1_1") (pintype "passive"))
      (node (ref "C4") (pin "2") (pinfunction "2_2") (pintype "passive"))
      (node (ref "C46") (pin "1") (pinfunction "1_1") (pintype "passive"))
      (node (ref "D2") (pin "1") (pinfunction "A_1") (pintype "passive"))
      (node (ref "D3") (pin "1") (pinfunction "A_1") (pintype "passive"))
      (node (ref "J2") (pin "7") (pinfunction "7_7") (pintype "passive"))
      (node (ref "J3") (pin "1") (pinfunction "1_1") (pintype "passive"))
      (node (ref "J3") (pin "12") (pinfunction "12_12") (pintype "passive"))
      (node (ref "J3") (pin "15") (pinfunction "15_15") (pintype "passive"))
      (node (ref "J3") (pin "16") (pinfunction "16_16") (pintype "passive"))
      (node (ref "J3") (pin "2") (pinfunction "2_2") (pintype "passive"))
      (node (ref "J3") (pin "3") (pinfunction "3_3") (pintype "passive"))
      (node (ref "J3") (pin "4") (pinfunction "4_4") (pintype "passive"))
      (node (ref "J5") (pin "2") (pinfunction "2_2") (pintype "passive"))
      (node (ref "J5") (pin "4") (pinfunction "4_4") (pintype "passive"))
      (node (ref "P2") (pin "4") (pintype "passive"))
      (node (ref "P2") (pin "5") (pintype "passive"))
      (node (ref "R1") (pin "2") (pinfunction "2_2") (pintype "passive"))
      (node (ref "R14") (pin "2") (pinfunction "2_2") (pintype "passive"))
      (node (ref "R2") (pin "1") (pinfunction "1_1") (pintype "passive"))
      (node (ref "R22") (pin "2") (pinfunction "2_2") (pintype "passive"))
      (node (ref "R24") (pin "2") (pinfunction "2_2") (pintype "passive"))
      (node (ref "R28") (pin "1") (pintype "passive"))
      (node (ref "R29") (pin "1") (pintype "passive"))
      (node (ref "R3") (pin "1") (pinfunction "1_1") (pintype "passive"))
      (node (ref "S3") (pin "3") (pinfunction "3_3") (pintype "passive"))
      (node (ref "U2") (pin "11") (pinfunction "VDD_5_11") (pintype "power_in"))
      (node (ref "U2") (pin "28") (pinfunction "VDD_4_28") (pintype "power_in"))
      (node (ref "U2") (pin "75") (pinfunction "VDD_2_75") (pintype "power_in"))
      (node (ref "U3") (pin "14") (pinfunction "VDD33/VIO_14") (pintype "power_in"))
    )
    (net (code "121") (name "5V_in") (class "Default")
      (node (ref "F2") (pin "1") (pinfunction "1_1") (pintype "passive"))
      (node (ref "P6") (pin "A4") (pinfunction "VBUS_A4") (pintype "bidirectional"))
      (node (ref "P6") (pin "B4") (pinfunction "VBUS_B4") (pintype "bidirectional"))
      (node (ref "P7") (pin "A4") (pinfunction "VBUS_A4") (pintype "bidirectional"))
      (node (ref "P7") (pin "B4") (pinfunction "VBUS_B4") (pintype "bidirectional"))
      (node (ref "P9") (pin "A4") (pinfunction "VBUS_A4") (pintype "bidirectional"))
      (node (ref "P9") (pin "B4") (pinfunction "VBUS_B4") (pintype "bidirectional"))
    )
    (net (code "122") (name "GND") (class "Default")
      (node (ref "C1") (pin "1") (pinfunction "1_1") (pintype "passive"))
      (node (ref "C10") (pin "1") (pinfunction "1_1") (pintype "passive"))
      (node (ref "C11") (pin "1") (pinfunction "1_1") (pintype "passive"))
      (node (ref "C12") (pin "2") (pinfunction "2_2") (pintype "passive"))
      (node (ref "C13") (pin "2") (pinfunction "2_2") (pintype "passive"))
      (node (ref "C14") (pin "1") (pinfunction "1_1") (pintype "passive"))
      (node (ref "C2") (pin "1") (pinfunction "1_1") (pintype "passive"))
      (node (ref "C21") (pin "2") (pinfunction "2_2") (pintype "passive"))
      (node (ref "C3") (pin "2") (pinfunction "2_2") (pintype "passive"))
      (node (ref "C31") (pin "1") (pinfunction "1_1") (pintype "passive"))
      (node (ref "C32") (pin "1") (pinfunction "1_1") (pintype "passive"))
      (node (ref "C4") (pin "1") (pinfunction "1_1") (pintype "passive"))
      (node (ref "C46") (pin "2") (pinfunction "2_2") (pintype "passive"))
      (node (ref "C5") (pin "2") (pinfunction "2_2") (pintype "passive"))
      (node (ref "C6") (pin "2") (pinfunction "2_2") (pintype "passive"))
      (node (ref "C7") (pin "1") (pinfunction "1_1") (pintype "passive"))
      (node (ref "C8") (pin "1") (pinfunction "1_1") (pintype "passive"))
      (node (ref "C9") (pin "1") (pinfunction "1_1") (pintype "passive"))
      (node (ref "J2") (pin "5") (pinfunction "5_5") (pintype "passive"))
      (node (ref "J2") (pin "6") (pinfunction "6_6") (pintype "passive"))
      (node (ref "J3") (pin "20") (pinfunction "20_20") (pintype "passive"))
      (node (ref "J3") (pin "22") (pinfunction "22_22") (pintype "passive"))
      (node (ref "J3") (pin "25") (pinfunction "25_25") (pintype "passive"))
      (node (ref "J3") (pin "26") (pinfunction "26_26") (pintype "passive"))
      (node (ref "J3") (pin "7") (pinfunction "7_7") (pintype "passive"))
      (node (ref "J3") (pin "8") (pinfunction "8_8") (pintype "passive"))
      (node (ref "J3") (pin "9") (pinfunction "9_9") (pintype "passive"))
      (node (ref "J4") (pin "7") (pinfunction "7_7") (pintype "passive"))
      (node (ref "J5") (pin "6") (pinfunction "6_6") (pintype "passive"))
      (node (ref "J5") (pin "7") (pinfunction "7_7") (pintype "passive"))
      (node (ref "J7") (pin "4") (pinfunction "4_4") (pintype "passive"))
      (node (ref "P2") (pin "8") (pintype "passive"))
      (node (ref "P6") (pin "A1") (pinfunction "GND_A1") (pintype "bidirectional"))
      (node (ref "P6") (pin "B1") (pinfunction "GND_B1") (pintype "bidirectional"))
      (node (ref "P7") (pin "A1") (pinfunction "GND_A1") (pintype "bidirectional"))
      (node (ref "P7") (pin "B1") (pinfunction "GND_B1") (pintype "bidirectional"))
      (node (ref "P9") (pin "A1") (pinfunction "GND_A1") (pintype "bidirectional"))
      (node (ref "P9") (pin "B1") (pinfunction "GND_B1") (pintype "bidirectional"))
      (node (ref "PWR") (pin "2") (pinfunction "K_2") (pintype "passive"))
      (node (ref "R10") (pin "2") (pinfunction "2_2") (pintype "passive"))
      (node (ref "R11") (pin "2") (pinfunction "2_2") (pintype "passive"))
      (node (ref "R18") (pin "1") (pinfunction "1_1") (pintype "passive"))
      (node (ref "R20") (pin "1") (pinfunction "1_1") (pintype "passive"))
      (node (ref "R21") (pin "1") (pinfunction "1_1") (pintype "passive"))
      (node (ref "R31") (pin "1") (pinfunction "1_1") (pintype "passive"))
      (node (ref "R8") (pin "1") (pinfunction "1_1") (pintype "passive"))
      (node (ref "R9") (pin "1") (pinfunction "1_1") (pintype "passive"))
      (node (ref "S1") (pin "3") (pinfunction "B1_3") (pintype "passive"))
      (node (ref "S2") (pin "3") (pinfunction "B1_3") (pintype "passive"))
      (node (ref "S5") (pin "2") (pinfunction "2_2") (pintype "passive"))
      (node (ref "U1") (pin "1") (pinfunction "GND_1") (pintype "passive"))
      (node (ref "U2") (pin "10") (pinfunction "VSS_5_10") (pintype "power_in"))
      (node (ref "U2") (pin "19") (pinfunction "VSSA_19") (pintype "power_in"))
      (node (ref "U2") (pin "27") (pinfunction "VSS_4_27") (pintype "power_in"))
      (node (ref "U2") (pin "49") (pinfunction "VSS_1_49") (pintype "power_in"))
      (node (ref "U2") (pin "74") (pinfunction "VSS_2_74") (pintype "power_in"))
      (node (ref "U2") (pin "99") (pinfunction "VSS_3_99") (pintype "power_in"))
      (node (ref "U3") (pin "18") (pinfunction "VSS/GND_18") (pintype "power_in"))
    )
    (net (code "123") (name "Net-(D2-K)") (class "Default")
      (node (ref "D2") (pin "2") (pinfunction "K_2") (pintype "passive"))
      (node (ref "R13") (pin "2") (pinfunction "2_2") (pintype "passive"))
    )
    (net (code "124") (name "Net-(D3-K)") (class "Default")
      (node (ref "D3") (pin "2") (pinfunction "K_2") (pintype "passive"))
      (node (ref "R21") (pin "2") (pinfunction "2_2") (pintype "passive"))
    )
    (net (code "125") (name "Net-(J3-Pad6)") (class "Default")
      (node (ref "J3") (pin "6") (pinfunction "6_6") (pintype "passive"))
      (node (ref "R5") (pin "1") (pinfunction "1_1") (pintype "passive"))
    )
    (net (code "126") (name "Net-(J3-Pad10)") (class "Default")
      (node (ref "J3") (pin "10") (pinfunction "10_10") (pintype "passive"))
      (node (ref "J5") (pin "1") (pinfunction "1_1") (pintype "passive"))
    )
    (net (code "127") (name "Net-(LED1-A)") (class "Default")
      (node (ref "LED1") (pin "1") (pinfunction "A_1") (pintype "passive"))
      (node (ref "R2") (pin "2") (pinfunction "2_2") (pintype "passive"))
    )
    (net (code "128") (name "Net-(LED2-A)") (class "Default")
      (node (ref "LED2") (pin "1") (pinfunction "A_1") (pintype "passive"))
      (node (ref "R3") (pin "2") (pinfunction "2_2") (pintype "passive"))
    )
    (net (code "129") (name "Net-(P2-Pad9)") (class "Default")
      (node (ref "P2") (pin "9") (pintype "passive"))
      (node (ref "R28") (pin "2") (pintype "passive"))
    )
    (net (code "130") (name "Net-(P2-Pad12)") (class "Default")
      (node (ref "P2") (pin "12") (pintype "passive"))
      (node (ref "R29") (pin "2") (pintype "passive"))
    )
    (net (code "131") (name "Net-(P6-CC-PadA5)") (class "Default")
      (node (ref "P6") (pin "A5") (pinfunction "CC_A5") (pintype "bidirectional"))
      (node (ref "R20") (pin "2") (pinfunction "2_2") (pintype "passive"))
    )
    (net (code "132") (name "Net-(P6-CC-PadB5)") (class "Default")
      (node (ref "P6") (pin "B5") (pinfunction "CC_B5") (pintype "bidirectional"))
      (node (ref "R31") (pin "2") (pinfunction "2_2") (pintype "passive"))
    )
    (net (code "133") (name "Net-(P7-CC-PadA5)") (class "Default")
      (node (ref "P7") (pin "A5") (pinfunction "CC_A5") (pintype "bidirectional"))
      (node (ref "R8") (pin "2") (pinfunction "2_2") (pintype "passive"))
    )
    (net (code "134") (name "Net-(P7-CC-PadB5)") (class "Default")
      (node (ref "P7") (pin "B5") (pinfunction "CC_B5") (pintype "bidirectional"))
      (node (ref "R9") (pin "2") (pinfunction "2_2") (pintype "passive"))
    )
    (net (code "135") (name "Net-(P9-CC-PadA5)") (class "Default")
      (node (ref "P9") (pin "A5") (pinfunction "CC_A5") (pintype "bidirectional"))
      (node (ref "R10") (pin "1") (pinfunction "1_1") (pintype "passive"))
    )
    (net (code "136") (name "Net-(P9-CC-PadB5)") (class "Default")
      (node (ref "P9") (pin "B5") (pinfunction "CC_B5") (pintype "bidirectional"))
      (node (ref "R11") (pin "1") (pinfunction "1_1") (pintype "passive"))
    )
    (net (code "137") (name "Net-(PWR-A)") (class "Default")
      (node (ref "PWR") (pin "1") (pinfunction "A_1") (pintype "passive"))
      (node (ref "R1") (pin "1") (pinfunction "1_1") (pintype "passive"))
    )
    (net (code "138") (name "Net-(U1-VOUT)") (class "Default")
      (node (ref "C13") (pin "1") (pinfunction "1_1") (pintype "passive"))
      (node (ref "S3") (pin "1") (pinfunction "1_1") (pintype "passive"))
      (node (ref "U1") (pin "2") (pinfunction "VOUT_2") (pintype "passive"))
    )
    (net (code "139") (name "unconnected-(P2-Pad7)") (class "Default")
      (node (ref "P2") (pin "7") (pintype "passive"))
    )
    (net (code "140") (name "unconnected-(P6-RFU1-PadA8)") (class "Default")
      (node (ref "P6") (pin "A8") (pinfunction "RFU1_A8") (pintype "bidirectional+no_connect"))
    )
    (net (code "141") (name "unconnected-(P6-RFU1-PadB8)") (class "Default")
      (node (ref "P6") (pin "B8") (pinfunction "RFU1_B8") (pintype "bidirectional+no_connect"))
    )
    (net (code "142") (name "unconnected-(P7-RFU1-PadA8)") (class "Default")
      (node (ref "P7") (pin "A8") (pinfunction "RFU1_A8") (pintype "bidirectional+no_connect"))
    )
    (net (code "143") (name "unconnected-(P7-RFU1-PadB8)") (class "Default")
      (node (ref "P7") (pin "B8") (pinfunction "RFU1_B8") (pintype "bidirectional+no_connect"))
    )
    (net (code "144") (name "unconnected-(P9-RFU1-PadA8)") (class "Default")
      (node (ref "P9") (pin "A8") (pinfunction "RFU1_A8") (pintype "bidirectional+no_connect"))
    )
    (net (code "145") (name "unconnected-(P9-RFU1-PadB8)") (class "Default")
      (node (ref "P9") (pin "B8") (pinfunction "RFU1_B8") (pintype "bidirectional+no_connect"))
    )
    (net (code "146") (name "unconnected-(S1-A1-Pad4)") (class "Default")
      (node (ref "S1") (pin "4") (pinfunction "A1_4") (pintype "passive"))
    )
    (net (code "147") (name "unconnected-(S1-B0-Pad2)") (class "Default")
      (node (ref "S1") (pin "2") (pinfunction "B0_2") (pintype "passive"))
    )
    (net (code "148") (name "unconnected-(S2-A1-Pad4)") (class "Default")
      (node (ref "S2") (pin "4") (pinfunction "A1_4") (pintype "passive"))
    )
    (net (code "149") (name "unconnected-(S2-B0-Pad2)") (class "Default")
      (node (ref "S2") (pin "2") (pinfunction "B0_2") (pintype "passive"))
    )
    (net (code "150") (name "unconnected-(S3-Pad2)") (class "Default")
      (node (ref "S3") (pin "2") (pinfunction "2_2") (pintype "passive"))
    )
    (net (code "151") (name "unconnected-(U3-PA5{slash}UART1_CTS{slash}PA1_(no5V)-Pad2)") (class "Default")
      (node (ref "U3") (pin "2") (pinfunction "PA5/UART1_CTS/PA1_(no5V)_2") (pintype "bidirectional+no_connect"))
    )
    (net (code "152") (name "unconnected-(U3-PB12{slash}SPI2_NSS{slash}CAN2_RX-Pad5)") (class "Default")
      (node (ref "U3") (pin "5") (pinfunction "PB12/SPI2_NSS/CAN2_RX_5") (pintype "bidirectional+no_connect"))
    )
    (net (code "153") (name "unconnected-(U3-PB14{slash}SPI2_MISO{slash}UART3_RTS-Pad7)") (class "Default")
      (node (ref "U3") (pin "7") (pinfunction "PB14/SPI2_MISO/UART3_RTS_7") (pintype "bidirectional+no_connect"))
    )
    (net (code "154") (name "unconnected-(U3-PB15{slash}SPI2_MOSI{slash}UART1_TX-Pad8)") (class "Default")
      (node (ref "U3") (pin "8") (pinfunction "PB15/SPI2_MOSI/UART1_TX_8") (pintype "bidirectional+no_connect"))
    )
  )
)
